# Sheet1_Young.net
KiCad netlist of a schematic drawn in Altium Designer
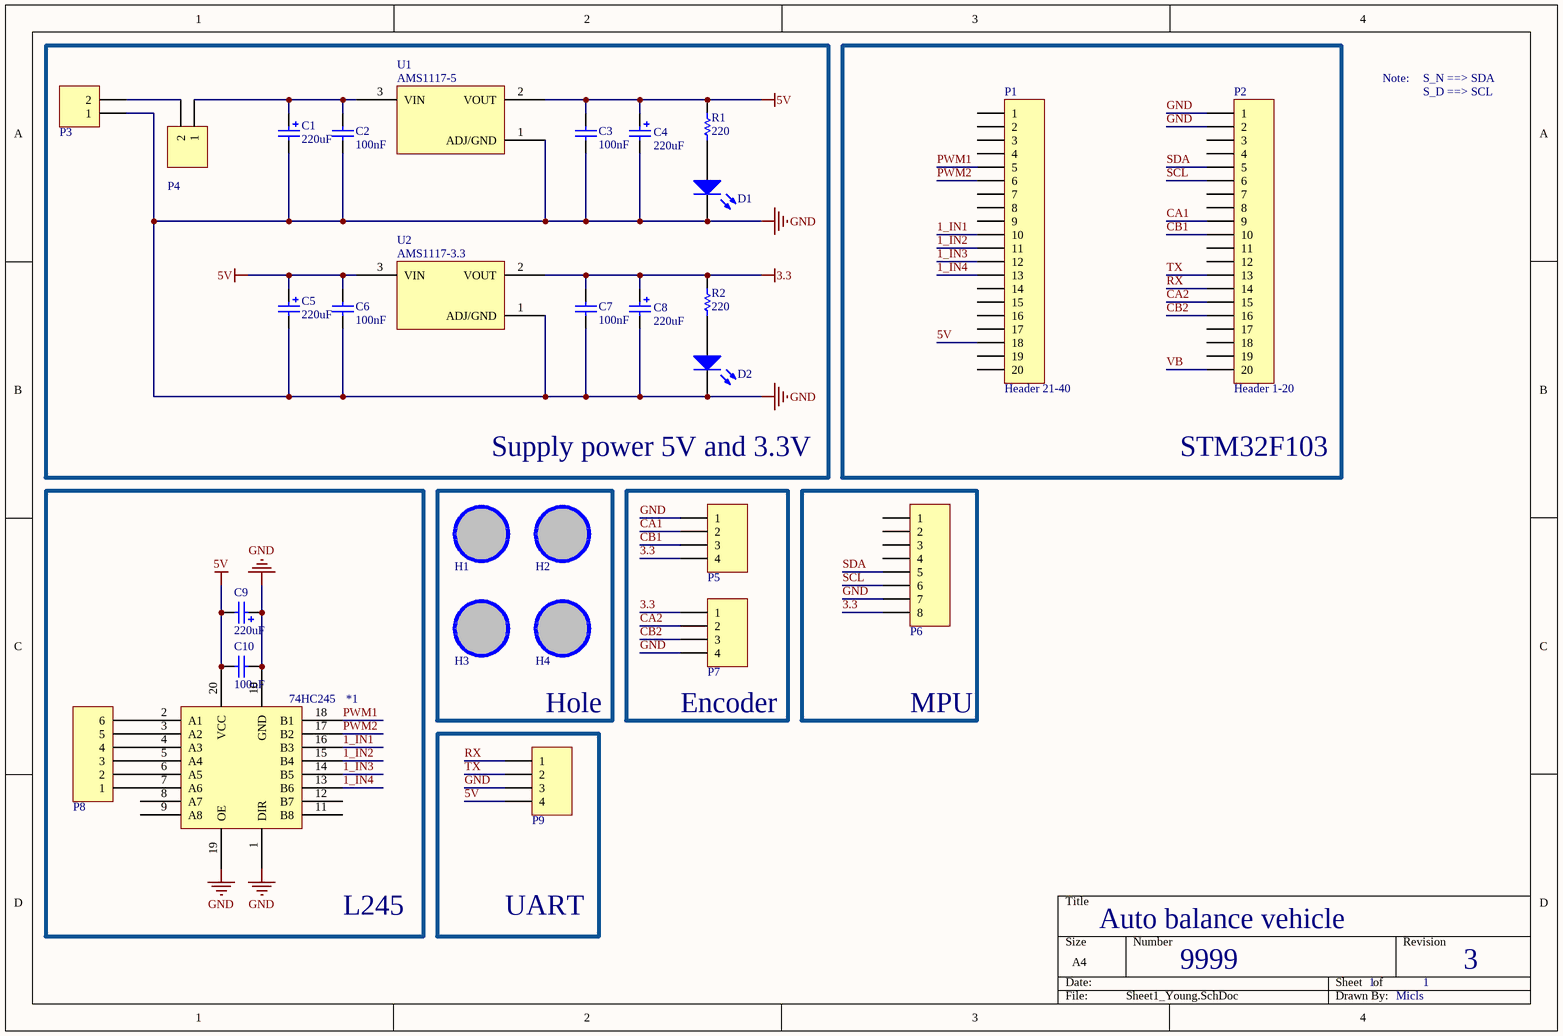
[diagram p0: Sheet1_Young.SchDoc]

(export (version "E")
  (design (tool "Eeschema 10.0.6"))
  (components
    (comp (ref "*1")
      (value "74HC245")
      (footprint "DIP20-3D")
      (libsource (lib "Bus Transceiver") (part "74HC245"))
    )
    (comp (ref "C1")
      (value "220uF")
      (footprint "CAP ALU SIZE B")
      (description "Polarized Capacitor (Radial)")
      (fields (field (name "Comment") "Cap Pol SMD"))
      (libsource (lib "PIF_Library") (part "Cap Pol SMD"))
    )
    (comp (ref "C2")
      (value "100nF")
      (footprint "CAP-SM-0805")
      (description "Capacitor")
      (fields (field (name "Comment") "Cap Non-Pol SMD"))
      (libsource (lib "PIF_Library") (part "Cap Non-Pol SMD"))
    )
    (comp (ref "C3")
      (value "100nF")
      (footprint "CAP-SM-0805")
      (description "Capacitor")
      (fields (field (name "Comment") "Cap Non-Pol SMD"))
      (libsource (lib "PIF_Library") (part "Cap Non-Pol SMD"))
    )
    (comp (ref "C4")
      (value "220uF")
      (footprint "CAP ALU SIZE B")
      (description "Polarized Capacitor (Radial)")
      (fields (field (name "Comment") "Cap Pol SMD"))
      (libsource (lib "PIF_Library") (part "Cap Pol SMD"))
    )
    (comp (ref "C5")
      (value "220uF")
      (footprint "CAP ALU SIZE B")
      (description "Polarized Capacitor (Radial)")
      (fields (field (name "Comment") "Cap Pol SMD"))
      (libsource (lib "PIF_Library") (part "Cap Pol SMD"))
    )
    (comp (ref "C6")
      (value "100nF")
      (footprint "CAP-SM-0805")
      (description "Capacitor")
      (fields (field (name "Comment") "Cap Non-Pol SMD"))
      (libsource (lib "PIF_Library") (part "Cap Non-Pol SMD"))
    )
    (comp (ref "C7")
      (value "100nF")
      (footprint "CAP-SM-0805")
      (description "Capacitor")
      (fields (field (name "Comment") "Cap Non-Pol SMD"))
      (libsource (lib "PIF_Library") (part "Cap Non-Pol SMD"))
    )
    (comp (ref "C8")
      (value "220uF")
      (footprint "CAP ALU SIZE B")
      (description "Polarized Capacitor (Radial)")
      (fields (field (name "Comment") "Cap Pol SMD"))
      (libsource (lib "PIF_Library") (part "Cap Pol SMD"))
    )
    (comp (ref "C9")
      (value "220uF")
      (footprint "CAP ALU SIZE B")
      (description "Polarized Capacitor (Radial)")
      (fields (field (name "Comment") "Cap Pol SMD"))
      (libsource (lib "PIF_Library") (part "Cap Pol SMD"))
    )
    (comp (ref "C10")
      (value "100nF")
      (footprint "CAP-SM-0805")
      (description "Capacitor")
      (fields (field (name "Comment") "Cap Non-Pol SMD"))
      (libsource (lib "PIF_Library") (part "Cap Non-Pol SMD"))
    )
    (comp (ref "D1")
      (value "LED SMD")
      (footprint "LED_0805_Blue")
      (description "LED")
      (libsource (lib "PIF_Library") (part "LED SMD"))
    )
    (comp (ref "D2")
      (value "LED SMD")
      (footprint "LED_0805_Blue")
      (description "LED")
      (libsource (lib "PIF_Library") (part "LED SMD"))
    )
    (comp (ref "H1")
      (value "Hole")
      (footprint "LO KHOAN 3MM")
      (description "Hole 3mm")
      (libsource (lib "PIF_Library") (part "Hole"))
    )
    (comp (ref "H2")
      (value "Hole")
      (footprint "LO KHOAN 3MM")
      (description "Hole 3mm")
      (libsource (lib "PIF_Library") (part "Hole"))
    )
    (comp (ref "H3")
      (value "Hole")
      (footprint "LO KHOAN 3MM")
      (description "Hole 3mm")
      (libsource (lib "PIF_Library") (part "Hole"))
    )
    (comp (ref "H4")
      (value "Hole")
      (footprint "LO KHOAN 3MM")
      (description "Hole 3mm")
      (libsource (lib "PIF_Library") (part "Hole"))
    )
    (comp (ref "P1")
      (value "Header 21-40")
      (footprint "HDR1X20")
      (description "Header, 20-Pin")
      (fields (field (name "PUBLISHER") "Altium Limited"))
      (libsource (lib "Miscellaneous Connectors") (part "Header 20"))
    )
    (comp (ref "P2")
      (value "Header 1-20")
      (footprint "HDR1X20")
      (description "Header, 20-Pin")
      (fields (field (name "PUBLISHER") "Altium Limited"))
      (libsource (lib "Miscellaneous Connectors") (part "Header 20"))
    )
    (comp (ref "P3")
      (value "Domino 2")
      (footprint "DOMINO 2- 5mm")
      (description "Domino, 2-Pin")
      (fields (field (name "PUBLISHER") "Altium Limited"))
      (libsource (lib "PIF_Library") (part "Domino 2"))
    )
    (comp (ref "P4")
      (value "Domino 2")
      (footprint "DOMINO 2- 5mm")
      (description "Domino, 2-Pin")
      (fields (field (name "PUBLISHER") "Altium Limited"))
      (libsource (lib "") (part "Domino 2_1"))
    )
    (comp (ref "P5")
      (value "Header 4")
      (footprint "JP4")
      (description "Header, 4-Pin")
      (fields (field (name "PUBLISHER") "Altium Limited"))
      (libsource (lib "PIF_Library") (part "Header 4"))
    )
    (comp (ref "P6")
      (value "Header 8")
      (footprint "JP8")
      (description "Header, 8-Pin")
      (fields (field (name "PUBLISHER") "Altium Limited"))
      (libsource (lib "PIF_Library") (part "Header 8"))
    )
    (comp (ref "P7")
      (value "Header 4")
      (footprint "JP4")
      (description "Header, 4-Pin")
      (fields (field (name "PUBLISHER") "Altium Limited"))
      (libsource (lib "PIF_Library") (part "Header 4"))
    )
    (comp (ref "P8")
      (value "Header 6")
      (footprint "JP6")
      (description "Header, 6-Pin")
      (fields (field (name "PUBLISHER") "Altium Limited"))
      (libsource (lib "PIF_Library") (part "Header 6"))
    )
    (comp (ref "P9")
      (value "Header 4")
      (footprint "JP4")
      (description "Header, 4-Pin")
      (fields (field (name "PUBLISHER") "Altium Limited"))
      (libsource (lib "PIF_Library") (part "Header 4"))
    )
    (comp (ref "R1")
      (value "220")
      (footprint "RES-SM-0805")
      (description "Resistor")
      (fields (field (name "Comment") "RESISTOR SMD"))
      (libsource (lib "PIF_Library") (part "RESISTOR SMD"))
    )
    (comp (ref "R2")
      (value "220")
      (footprint "RES-SM-0805")
      (description "Resistor")
      (fields (field (name "Comment") "RESISTOR SMD"))
      (libsource (lib "PIF_Library") (part "RESISTOR SMD"))
    )
    (comp (ref "U1")
      (value "AMS1117-5")
      (footprint "SOT230P700X180-4N")
      (fields (field (name "MP") "AMS1117-3.3") (field (name "MF") "NEC"))
      (libsource (lib "AMS1117-3.3") (part "AMS1117-3.3"))
    )
    (comp (ref "U2")
      (value "AMS1117-3.3")
      (footprint "SOT230P700X180-4N")
      (fields (field (name "MF") "NEC"))
      (libsource (lib "AMS1117-3.3") (part "AMS1117-3.3"))
    )
  )
  (nets
    (net (code "1") (name "/1_IN1") (class "Default")
      (node (ref "*1") (pin "16") (pinfunction "B3_16") (pintype "passive"))
      (node (ref "P1") (pin "10") (pinfunction "10_10") (pintype "passive"))
    )
    (net (code "2") (name "/1_IN2") (class "Default")
      (node (ref "*1") (pin "15") (pinfunction "B4_15") (pintype "passive"))
      (node (ref "P1") (pin "11") (pinfunction "11_11") (pintype "passive"))
    )
    (net (code "3") (name "/1_IN3") (class "Default")
      (node (ref "*1") (pin "14") (pinfunction "B5_14") (pintype "passive"))
      (node (ref "P1") (pin "12") (pinfunction "12_12") (pintype "passive"))
    )
    (net (code "4") (name "/1_IN4") (class "Default")
      (node (ref "*1") (pin "13") (pinfunction "B6_13") (pintype "passive"))
      (node (ref "P1") (pin "13") (pinfunction "13_13") (pintype "passive"))
    )
    (net (code "5") (name "/CA1") (class "Default")
      (node (ref "P2") (pin "9") (pinfunction "9_9") (pintype "passive"))
      (node (ref "P5") (pin "2") (pinfunction "2_2") (pintype "passive"))
    )
    (net (code "6") (name "/CA2") (class "Default")
      (node (ref "P2") (pin "15") (pinfunction "15_15") (pintype "passive"))
      (node (ref "P7") (pin "2") (pinfunction "2_2") (pintype "passive"))
    )
    (net (code "7") (name "/CB1") (class "Default")
      (node (ref "P2") (pin "10") (pinfunction "10_10") (pintype "passive"))
      (node (ref "P5") (pin "3") (pinfunction "3_3") (pintype "passive"))
    )
    (net (code "8") (name "/CB2") (class "Default")
      (node (ref "P2") (pin "16") (pinfunction "16_16") (pintype "passive"))
      (node (ref "P7") (pin "3") (pinfunction "3_3") (pintype "passive"))
    )
    (net (code "9") (name "/PWM1") (class "Default")
      (node (ref "*1") (pin "18") (pinfunction "B1_18") (pintype "passive"))
      (node (ref "P1") (pin "5") (pinfunction "5_5") (pintype "passive"))
    )
    (net (code "10") (name "/PWM2") (class "Default")
      (node (ref "*1") (pin "17") (pinfunction "B2_17") (pintype "passive"))
      (node (ref "P1") (pin "6") (pinfunction "6_6") (pintype "passive"))
    )
    (net (code "11") (name "/RX") (class "Default")
      (node (ref "P2") (pin "14") (pinfunction "14_14") (pintype "passive"))
      (node (ref "P9") (pin "1") (pinfunction "1_1") (pintype "passive"))
    )
    (net (code "12") (name "/SCL") (class "Default")
      (node (ref "P2") (pin "6") (pinfunction "6_6") (pintype "passive"))
      (node (ref "P6") (pin "6") (pinfunction "6_6") (pintype "passive"))
    )
    (net (code "13") (name "/SDA") (class "Default")
      (node (ref "P2") (pin "5") (pinfunction "5_5") (pintype "passive"))
      (node (ref "P6") (pin "5") (pinfunction "5_5") (pintype "passive"))
    )
    (net (code "14") (name "/TX") (class "Default")
      (node (ref "P2") (pin "13") (pinfunction "13_13") (pintype "passive"))
      (node (ref "P9") (pin "2") (pinfunction "2_2") (pintype "passive"))
    )
    (net (code "15") (name "/VB") (class "Default")
      (node (ref "P2") (pin "20") (pinfunction "20_20") (pintype "passive"))
    )
    (net (code "16") (name "3.3") (class "Default")
      (node (ref "C7") (pin "1") (pinfunction "1_1") (pintype "passive"))
      (node (ref "C8") (pin "1") (pinfunction "1_1") (pintype "passive"))
      (node (ref "P5") (pin "4") (pinfunction "4_4") (pintype "passive"))
      (node (ref "P6") (pin "8") (pinfunction "8_8") (pintype "passive"))
      (node (ref "P7") (pin "1") (pinfunction "1_1") (pintype "passive"))
      (node (ref "R2") (pin "2") (pinfunction "2_2") (pintype "passive"))
      (node (ref "U2") (pin "2") (pinfunction "VOUT_2") (pintype "passive"))
    )
    (net (code "17") (name "5V") (class "Default")
      (node (ref "*1") (pin "20") (pinfunction "VCC_20") (pintype "passive"))
      (node (ref "C10") (pin "1") (pinfunction "1_1") (pintype "passive"))
      (node (ref "C3") (pin "1") (pinfunction "1_1") (pintype "passive"))
      (node (ref "C4") (pin "1") (pinfunction "1_1") (pintype "passive"))
      (node (ref "C5") (pin "1") (pinfunction "1_1") (pintype "passive"))
      (node (ref "C6") (pin "2") (pinfunction "2_2") (pintype "passive"))
      (node (ref "C9") (pin "2") (pinfunction "2_2") (pintype "passive"))
      (node (ref "P1") (pin "18") (pinfunction "18_18") (pintype "passive"))
      (node (ref "P9") (pin "4") (pinfunction "4_4") (pintype "passive"))
      (node (ref "R1") (pin "2") (pinfunction "2_2") (pintype "passive"))
      (node (ref "U1") (pin "2") (pinfunction "VOUT_2") (pintype "passive"))
      (node (ref "U2") (pin "3") (pinfunction "VIN_3") (pintype "passive"))
    )
    (net (code "18") (name "GND") (class "Default")
      (node (ref "*1") (pin "1") (pinfunction "DIR_1") (pintype "passive"))
      (node (ref "*1") (pin "10") (pinfunction "GND_10") (pintype "passive"))
      (node (ref "*1") (pin "19") (pinfunction "OE_19") (pintype "passive"))
      (node (ref "C1") (pin "2") (pinfunction "2_2") (pintype "passive"))
      (node (ref "C10") (pin "2") (pinfunction "2_2") (pintype "passive"))
      (node (ref "C2") (pin "1") (pinfunction "1_1") (pintype "passive"))
      (node (ref "C3") (pin "2") (pinfunction "2_2") (pintype "passive"))
      (node (ref "C4") (pin "2") (pinfunction "2_2") (pintype "passive"))
      (node (ref "C5") (pin "2") (pinfunction "2_2") (pintype "passive"))
      (node (ref "C6") (pin "1") (pinfunction "1_1") (pintype "passive"))
      (node (ref "C7") (pin "2") (pinfunction "2_2") (pintype "passive"))
      (node (ref "C8") (pin "2") (pinfunction "2_2") (pintype "passive"))
      (node (ref "C9") (pin "1") (pinfunction "1_1") (pintype "passive"))
      (node (ref "D1") (pin "2") (pinfunction "K_2") (pintype "passive"))
      (node (ref "D2") (pin "2") (pinfunction "K_2") (pintype "passive"))
      (node (ref "P2") (pin "1") (pinfunction "1_1") (pintype "passive"))
      (node (ref "P2") (pin "2") (pinfunction "2_2") (pintype "passive"))
      (node (ref "P3") (pin "1") (pinfunction "1_1") (pintype "passive"))
      (node (ref "P5") (pin "1") (pinfunction "1_1") (pintype "passive"))
      (node (ref "P6") (pin "7") (pinfunction "7_7") (pintype "passive"))
      (node (ref "P7") (pin "4") (pinfunction "4_4") (pintype "passive"))
      (node (ref "P9") (pin "3") (pinfunction "3_3") (pintype "passive"))
      (node (ref "U1") (pin "1") (pinfunction "ADJ/GND_1") (pintype "passive"))
      (node (ref "U2") (pin "1") (pinfunction "ADJ/GND_1") (pintype "passive"))
    )
    (net (code "19") (name "Net-(*1-A1)") (class "Default")
      (node (ref "*1") (pin "2") (pinfunction "A1_2") (pintype "passive"))
      (node (ref "P8") (pin "6") (pinfunction "6_6") (pintype "passive"))
    )
    (net (code "20") (name "Net-(*1-A2)") (class "Default")
      (node (ref "*1") (pin "3") (pinfunction "A2_3") (pintype "passive"))
      (node (ref "P8") (pin "5") (pinfunction "5_5") (pintype "passive"))
    )
    (net (code "21") (name "Net-(*1-A3)") (class "Default")
      (node (ref "*1") (pin "4") (pinfunction "A3_4") (pintype "passive"))
      (node (ref "P8") (pin "4") (pinfunction "4_4") (pintype "passive"))
    )
    (net (code "22") (name "Net-(*1-A4)") (class "Default")
      (node (ref "*1") (pin "5") (pinfunction "A4_5") (pintype "passive"))
      (node (ref "P8") (pin "3") (pinfunction "3_3") (pintype "passive"))
    )
    (net (code "23") (name "Net-(*1-A5)") (class "Default")
      (node (ref "*1") (pin "6") (pinfunction "A5_6") (pintype "passive"))
      (node (ref "P8") (pin "2") (pinfunction "2_2") (pintype "passive"))
    )
    (net (code "24") (name "Net-(*1-A6)") (class "Default")
      (node (ref "*1") (pin "7") (pinfunction "A6_7") (pintype "passive"))
      (node (ref "P8") (pin "1") (pinfunction "1_1") (pintype "passive"))
    )
    (net (code "25") (name "Net-(D1-A)") (class "Default")
      (node (ref "D1") (pin "1") (pinfunction "A_1") (pintype "passive"))
      (node (ref "R1") (pin "1") (pinfunction "1_1") (pintype "passive"))
    )
    (net (code "26") (name "Net-(D2-A)") (class "Default")
      (node (ref "D2") (pin "1") (pinfunction "A_1") (pintype "passive"))
      (node (ref "R2") (pin "1") (pinfunction "1_1") (pintype "passive"))
    )
    (net (code "27") (name "Net-(P3-Pad2)") (class "Default")
      (node (ref "P3") (pin "2") (pinfunction "2_2") (pintype "passive"))
      (node (ref "P4") (pin "2") (pinfunction "2_2") (pintype "passive"))
    )
    (net (code "28") (name "Net-(U1-VIN)") (class "Default")
      (node (ref "C1") (pin "1") (pinfunction "1_1") (pintype "passive"))
      (node (ref "C2") (pin "2") (pinfunction "2_2") (pintype "passive"))
      (node (ref "P4") (pin "1") (pinfunction "1_1") (pintype "passive"))
      (node (ref "U1") (pin "3") (pinfunction "VIN_3") (pintype "passive"))
    )
    (net (code "29") (name "unconnected-(*1-A7-Pad8)") (class "Default")
      (node (ref "*1") (pin "8") (pinfunction "A7_8") (pintype "passive"))
    )
    (net (code "30") (name "unconnected-(*1-A8-Pad9)") (class "Default")
      (node (ref "*1") (pin "9") (pinfunction "A8_9") (pintype "passive"))
    )
    (net (code "31") (name "unconnected-(*1-B7-Pad12)") (class "Default")
      (node (ref "*1") (pin "12") (pinfunction "B7_12") (pintype "passive"))
    )
    (net (code "32") (name "unconnected-(*1-B8-Pad11)") (class "Default")
      (node (ref "*1") (pin "11") (pinfunction "B8_11") (pintype "passive"))
    )
    (net (code "33") (name "unconnected-(H1-Pad1)") (class "Default")
      (node (ref "H1") (pin "1") (pinfunction "1_1") (pintype "passive"))
    )
    (net (code "34") (name "unconnected-(H2-Pad1)") (class "Default")
      (node (ref "H2") (pin "1") (pinfunction "1_1") (pintype "passive"))
    )
    (net (code "35") (name "unconnected-(H3-Pad1)") (class "Default")
      (node (ref "H3") (pin "1") (pinfunction "1_1") (pintype "passive"))
    )
    (net (code "36") (name "unconnected-(H4-Pad1)") (class "Default")
      (node (ref "H4") (pin "1") (pinfunction "1_1") (pintype "passive"))
    )
    (net (code "37") (name "unconnected-(P1-Pad1)") (class "Default")
      (node (ref "P1") (pin "1") (pinfunction "1_1") (pintype "passive"))
    )
    (net (code "38") (name "unconnected-(P1-Pad2)") (class "Default")
      (node (ref "P1") (pin "2") (pinfunction "2_2") (pintype "passive"))
    )
    (net (code "39") (name "unconnected-(P1-Pad3)") (class "Default")
      (node (ref "P1") (pin "3") (pinfunction "3_3") (pintype "passive"))
    )
    (net (code "40") (name "unconnected-(P1-Pad4)") (class "Default")
      (node (ref "P1") (pin "4") (pinfunction "4_4") (pintype "passive"))
    )
    (net (code "41") (name "unconnected-(P1-Pad7)") (class "Default")
      (node (ref "P1") (pin "7") (pinfunction "7_7") (pintype "passive"))
    )
    (net (code "42") (name "unconnected-(P1-Pad8)") (class "Default")
      (node (ref "P1") (pin "8") (pinfunction "8_8") (pintype "passive"))
    )
    (net (code "43") (name "unconnected-(P1-Pad9)") (class "Default")
      (node (ref "P1") (pin "9") (pinfunction "9_9") (pintype "passive"))
    )
    (net (code "44") (name "unconnected-(P1-Pad14)") (class "Default")
      (node (ref "P1") (pin "14") (pinfunction "14_14") (pintype "passive"))
    )
    (net (code "45") (name "unconnected-(P1-Pad15)") (class "Default")
      (node (ref "P1") (pin "15") (pinfunction "15_15") (pintype "passive"))
    )
    (net (code "46") (name "unconnected-(P1-Pad16)") (class "Default")
      (node (ref "P1") (pin "16") (pinfunction "16_16") (pintype "passive"))
    )
    (net (code "47") (name "unconnected-(P1-Pad17)") (class "Default")
      (node (ref "P1") (pin "17") (pinfunction "17_17") (pintype "passive"))
    )
    (net (code "48") (name "unconnected-(P1-Pad19)") (class "Default")
      (node (ref "P1") (pin "19") (pinfunction "19_19") (pintype "passive"))
    )
    (net (code "49") (name "unconnected-(P1-Pad20)") (class "Default")
      (node (ref "P1") (pin "20") (pinfunction "20_20") (pintype "passive"))
    )
    (net (code "50") (name "unconnected-(P2-Pad3)") (class "Default")
      (node (ref "P2") (pin "3") (pinfunction "3_3") (pintype "passive"))
    )
    (net (code "51") (name "unconnected-(P2-Pad4)") (class "Default")
      (node (ref "P2") (pin "4") (pinfunction "4_4") (pintype "passive"))
    )
    (net (code "52") (name "unconnected-(P2-Pad7)") (class "Default")
      (node (ref "P2") (pin "7") (pinfunction "7_7") (pintype "passive"))
    )
    (net (code "53") (name "unconnected-(P2-Pad8)") (class "Default")
      (node (ref "P2") (pin "8") (pinfunction "8_8") (pintype "passive"))
    )
    (net (code "54") (name "unconnected-(P2-Pad11)") (class "Default")
      (node (ref "P2") (pin "11") (pinfunction "11_11") (pintype "passive"))
    )
    (net (code "55") (name "unconnected-(P2-Pad12)") (class "Default")
      (node (ref "P2") (pin "12") (pinfunction "12_12") (pintype "passive"))
    )
    (net (code "56") (name "unconnected-(P2-Pad17)") (class "Default")
      (node (ref "P2") (pin "17") (pinfunction "17_17") (pintype "passive"))
    )
    (net (code "57") (name "unconnected-(P2-Pad18)") (class "Default")
      (node (ref "P2") (pin "18") (pinfunction "18_18") (pintype "passive"))
    )
    (net (code "58") (name "unconnected-(P2-Pad19)") (class "Default")
      (node (ref "P2") (pin "19") (pinfunction "19_19") (pintype "passive"))
    )
    (net (code "59") (name "unconnected-(P6-Pad1)") (class "Default")
      (node (ref "P6") (pin "1") (pinfunction "1_1") (pintype "passive"))
    )
    (net (code "60") (name "unconnected-(P6-Pad2)") (class "Default")
      (node (ref "P6") (pin "2") (pinfunction "2_2") (pintype "passive"))
    )
    (net (code "61") (name "unconnected-(P6-Pad3)") (class "Default")
      (node (ref "P6") (pin "3") (pinfunction "3_3") (pintype "passive"))
    )
    (net (code "62") (name "unconnected-(P6-Pad4)") (class "Default")
      (node (ref "P6") (pin "4") (pinfunction "4_4") (pintype "passive"))
    )
  )
)
